# c_fan.net
KiCad netlist of a schematic drawn in Altium Designer
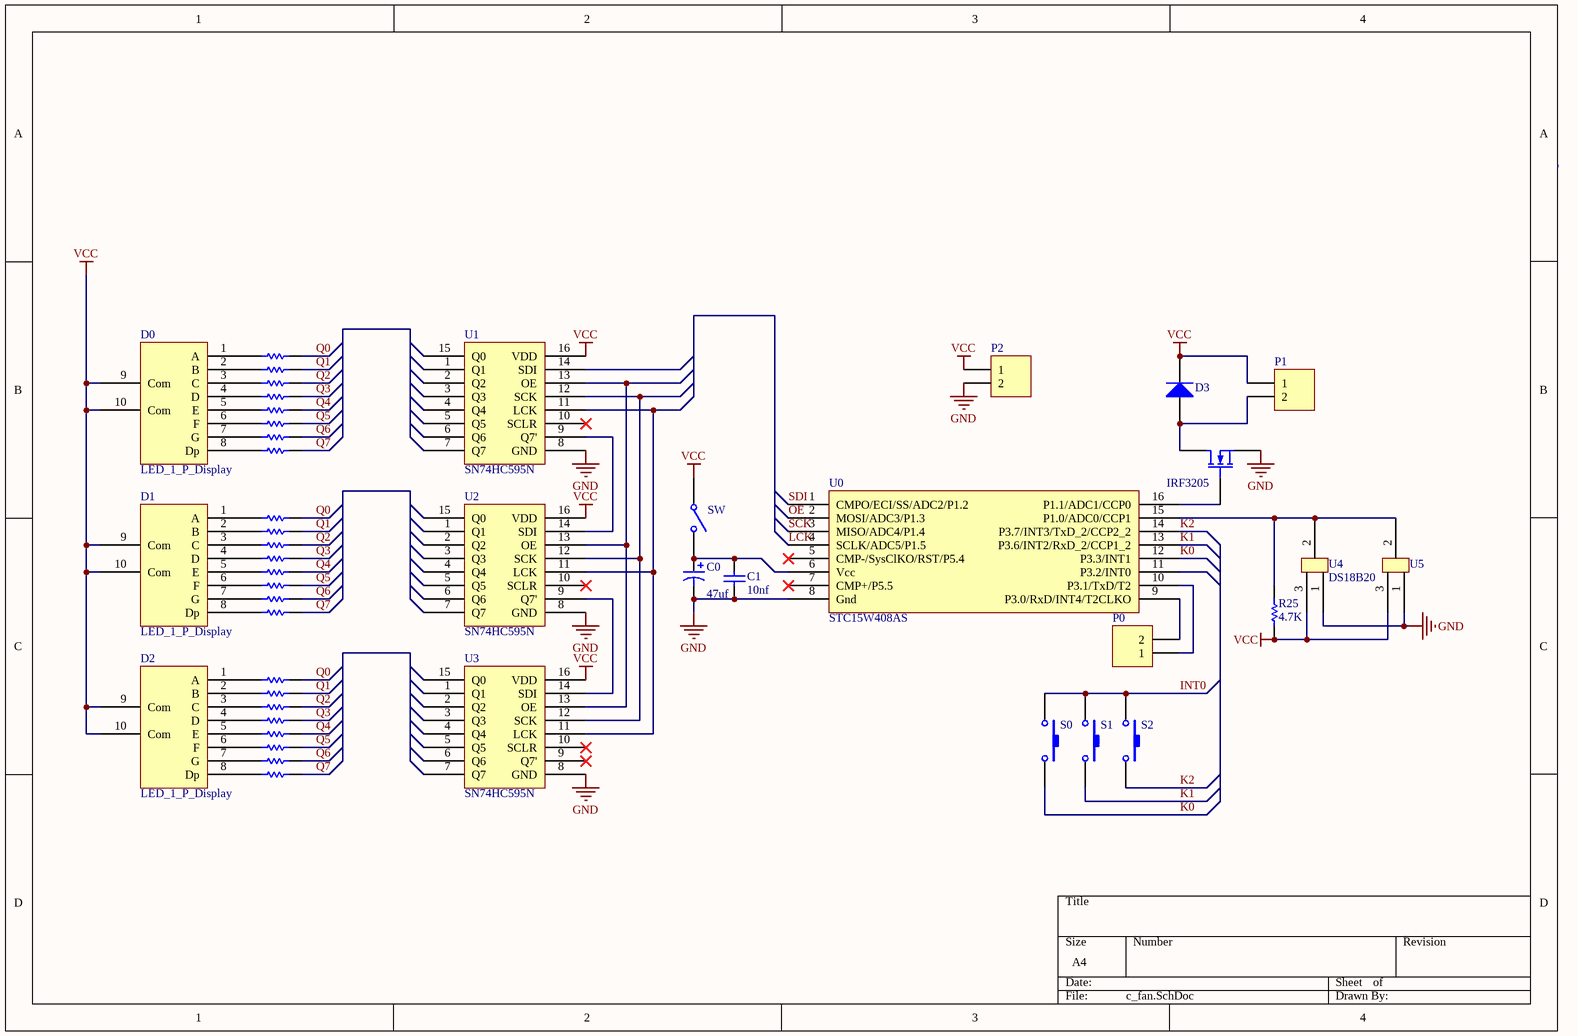
[diagram p0: c_fan.SchDoc]

(export (version "E")
  (design (tool "Eeschema 10.0.6"))
  (components
    (comp (ref "C0")
      (value "47uf")
      (footprint "C0805")
      (description "Polarized Capacitor (Surface Mount)")
      (fields (field (name "Comment") "Cap Pol3") (field (name "PUBLISHER") "Altium Limited"))
      (libsource (lib "Miscellaneous Devices") (part "Cap Pol3"))
    )
    (comp (ref "C1")
      (value "10nf")
      (footprint "C1206")
      (description "Capacitor (Semiconductor SIM Model)")
      (fields (field (name "Comment") "Cap Semi") (field (name "PUBLISHER") "Altium Limited"))
      (libsource (lib "Miscellaneous Devices") (part "Cap Semi"))
    )
    (comp (ref "D0")
      (value "LED_1_P_Display")
      (description "共阳一位")
      (libsource (lib "Self_establish") (part "LED_1_P_Display"))
    )
    (comp (ref "D1")
      (value "LED_1_P_Display")
      (description "共阳一位")
      (libsource (lib "Self_establish") (part "LED_1_P_Display"))
    )
    (comp (ref "D2")
      (value "LED_1_P_Display")
      (description "共阳一位")
      (libsource (lib "Self_establish") (part "LED_1_P_Display"))
    )
    (comp (ref "D3")
      (value "Diode")
      (footprint "SMC")
      (description "Default Diode")
      (fields (field (name "PUBLISHER") "Altium Limited"))
      (libsource (lib "Miscellaneous Devices") (part "Diode"))
    )
    (comp (ref "P0")
      (value "Header 2")
      (footprint "HDR1X2")
      (description "Header, 2-Pin")
      (fields (field (name "PUBLISHER") "Altium Limited"))
      (libsource (lib "Miscellaneous Connectors") (part "Header 2"))
    )
    (comp (ref "P1")
      (value "Header 2H")
      (footprint "HDR1X2H")
      (description "Header, 2-Pin, Right Angle")
      (fields (field (name "PUBLISHER") "Altium Limited"))
      (libsource (lib "Miscellaneous Connectors") (part "Header 2H"))
    )
    (comp (ref "P2")
      (value "Header 2H")
      (footprint "HDR1X2H")
      (description "Header, 2-Pin, Right Angle")
      (fields (field (name "PUBLISHER") "Altium Limited"))
      (libsource (lib "Miscellaneous Connectors") (part "Header 2H"))
    )
    (comp (ref "Q0")
      (value "IRF3205")
      (footprint "E3")
      (description "N-Channel MOSFET")
      (fields (field (name "PUBLISHER") "Altium Limited"))
      (libsource (lib "Miscellaneous Devices") (part "MOSFET-N"))
    )
    (comp (ref "R1")
      (value "Res1")
      (footprint "AXIAL-0.3")
      (description "Resistor")
      (fields (field (name "PUBLISHER") "Altium Limited"))
      (libsource (lib "Miscellaneous Devices") (part "Res1"))
    )
    (comp (ref "R2")
      (value "Res1")
      (footprint "AXIAL-0.3")
      (description "Resistor")
      (fields (field (name "PUBLISHER") "Altium Limited"))
      (libsource (lib "Miscellaneous Devices") (part "Res1"))
    )
    (comp (ref "R3")
      (value "Res1")
      (footprint "AXIAL-0.3")
      (description "Resistor")
      (fields (field (name "PUBLISHER") "Altium Limited"))
      (libsource (lib "Miscellaneous Devices") (part "Res1"))
    )
    (comp (ref "R4")
      (value "Res1")
      (footprint "AXIAL-0.3")
      (description "Resistor")
      (fields (field (name "PUBLISHER") "Altium Limited"))
      (libsource (lib "Miscellaneous Devices") (part "Res1"))
    )
    (comp (ref "R5")
      (value "Res1")
      (footprint "AXIAL-0.3")
      (description "Resistor")
      (fields (field (name "PUBLISHER") "Altium Limited"))
      (libsource (lib "Miscellaneous Devices") (part "Res1"))
    )
    (comp (ref "R6")
      (value "Res1")
      (footprint "AXIAL-0.3")
      (description "Resistor")
      (fields (field (name "PUBLISHER") "Altium Limited"))
      (libsource (lib "Miscellaneous Devices") (part "Res1"))
    )
    (comp (ref "R7")
      (value "Res1")
      (footprint "AXIAL-0.3")
      (description "Resistor")
      (fields (field (name "PUBLISHER") "Altium Limited"))
      (libsource (lib "Miscellaneous Devices") (part "Res1"))
    )
    (comp (ref "R8")
      (value "Res1")
      (footprint "AXIAL-0.3")
      (description "Resistor")
      (fields (field (name "PUBLISHER") "Altium Limited"))
      (libsource (lib "Miscellaneous Devices") (part "Res1"))
    )
    (comp (ref "R9")
      (value "Res1")
      (footprint "AXIAL-0.3")
      (description "Resistor")
      (fields (field (name "PUBLISHER") "Altium Limited"))
      (libsource (lib "Miscellaneous Devices") (part "Res1"))
    )
    (comp (ref "R10")
      (value "Res1")
      (footprint "AXIAL-0.3")
      (description "Resistor")
      (fields (field (name "PUBLISHER") "Altium Limited"))
      (libsource (lib "Miscellaneous Devices") (part "Res1"))
    )
    (comp (ref "R11")
      (value "Res1")
      (footprint "AXIAL-0.3")
      (description "Resistor")
      (fields (field (name "PUBLISHER") "Altium Limited"))
      (libsource (lib "Miscellaneous Devices") (part "Res1"))
    )
    (comp (ref "R12")
      (value "Res1")
      (footprint "AXIAL-0.3")
      (description "Resistor")
      (fields (field (name "PUBLISHER") "Altium Limited"))
      (libsource (lib "Miscellaneous Devices") (part "Res1"))
    )
    (comp (ref "R13")
      (value "Res1")
      (footprint "AXIAL-0.3")
      (description "Resistor")
      (fields (field (name "PUBLISHER") "Altium Limited"))
      (libsource (lib "Miscellaneous Devices") (part "Res1"))
    )
    (comp (ref "R14")
      (value "Res1")
      (footprint "AXIAL-0.3")
      (description "Resistor")
      (fields (field (name "PUBLISHER") "Altium Limited"))
      (libsource (lib "Miscellaneous Devices") (part "Res1"))
    )
    (comp (ref "R15")
      (value "Res1")
      (footprint "AXIAL-0.3")
      (description "Resistor")
      (fields (field (name "PUBLISHER") "Altium Limited"))
      (libsource (lib "Miscellaneous Devices") (part "Res1"))
    )
    (comp (ref "R16")
      (value "Res1")
      (footprint "AXIAL-0.3")
      (description "Resistor")
      (fields (field (name "PUBLISHER") "Altium Limited"))
      (libsource (lib "Miscellaneous Devices") (part "Res1"))
    )
    (comp (ref "R17")
      (value "Res1")
      (footprint "AXIAL-0.3")
      (description "Resistor")
      (fields (field (name "PUBLISHER") "Altium Limited"))
      (libsource (lib "Miscellaneous Devices") (part "Res1"))
    )
    (comp (ref "R18")
      (value "Res1")
      (footprint "AXIAL-0.3")
      (description "Resistor")
      (fields (field (name "PUBLISHER") "Altium Limited"))
      (libsource (lib "Miscellaneous Devices") (part "Res1"))
    )
    (comp (ref "R19")
      (value "Res1")
      (footprint "AXIAL-0.3")
      (description "Resistor")
      (fields (field (name "PUBLISHER") "Altium Limited"))
      (libsource (lib "Miscellaneous Devices") (part "Res1"))
    )
    (comp (ref "R20")
      (value "Res1")
      (footprint "AXIAL-0.3")
      (description "Resistor")
      (fields (field (name "PUBLISHER") "Altium Limited"))
      (libsource (lib "Miscellaneous Devices") (part "Res1"))
    )
    (comp (ref "R21")
      (value "Res1")
      (footprint "AXIAL-0.3")
      (description "Resistor")
      (fields (field (name "PUBLISHER") "Altium Limited"))
      (libsource (lib "Miscellaneous Devices") (part "Res1"))
    )
    (comp (ref "R22")
      (value "Res1")
      (footprint "AXIAL-0.3")
      (description "Resistor")
      (fields (field (name "PUBLISHER") "Altium Limited"))
      (libsource (lib "Miscellaneous Devices") (part "Res1"))
    )
    (comp (ref "R23")
      (value "Res1")
      (footprint "AXIAL-0.3")
      (description "Resistor")
      (fields (field (name "PUBLISHER") "Altium Limited"))
      (libsource (lib "Miscellaneous Devices") (part "Res1"))
    )
    (comp (ref "R24")
      (value "Res1")
      (footprint "AXIAL-0.3")
      (description "Resistor")
      (fields (field (name "PUBLISHER") "Altium Limited"))
      (libsource (lib "Miscellaneous Devices") (part "Res1"))
    )
    (comp (ref "R25")
      (value "4.7K")
      (footprint "AXIAL-0.3")
      (description "Resistor")
      (fields (field (name "Comment") "Res1") (field (name "PUBLISHER") "Altium Limited"))
      (libsource (lib "Miscellaneous Devices") (part "Res1"))
    )
    (comp (ref "S0")
      (value "SW-PB")
      (footprint "SPST-2")
      (description "Switch")
      (fields (field (name "PUBLISHER") "Altium Limited"))
      (libsource (lib "Miscellaneous Devices") (part "SW-PB"))
    )
    (comp (ref "S1")
      (value "SW-PB")
      (footprint "SPST-2")
      (description "Switch")
      (fields (field (name "PUBLISHER") "Altium Limited"))
      (libsource (lib "Miscellaneous Devices") (part "SW-PB"))
    )
    (comp (ref "S2")
      (value "SW-PB")
      (footprint "SPST-2")
      (description "Switch")
      (fields (field (name "PUBLISHER") "Altium Limited"))
      (libsource (lib "Miscellaneous Devices") (part "SW-PB"))
    )
    (comp (ref "SW")
      (value "SW-SPST")
      (footprint "SPST-2")
      (description "Single-Pole, Single-Throw Switch")
      (fields (field (name "PUBLISHER") "Altium Limited"))
      (libsource (lib "Miscellaneous Devices") (part "SW-SPST"))
    )
    (comp (ref "U0") (value "STC15W408AS") (libsource (lib "Self_establish") (part "STC15W408AS")))
    (comp (ref "U1") (value "SN74HC595N") (libsource (lib "Self_establish") (part "74HC595")))
    (comp (ref "U2") (value "SN74HC595N") (libsource (lib "Self_establish") (part "74HC595")))
    (comp (ref "U3") (value "SN74HC595N") (libsource (lib "Self_establish") (part "74HC595")))
    (comp (ref "U4") (value "DS18B20") (libsource (lib "Self_establish") (part "DS18B20")))
    (comp (ref "U5") (value "DS18B20") (libsource (lib "Self_establish") (part "DS18B20")))
  )
  (nets
    (net (code "1") (name "/INT0") (class "Default")
      (node (ref "S0") (pin "1") (pinfunction "1_1") (pintype "passive"))
      (node (ref "S1") (pin "1") (pinfunction "1_1") (pintype "passive"))
      (node (ref "S2") (pin "1") (pinfunction "1_1") (pintype "passive"))
    )
    (net (code "2") (name "/K0") (class "Default")
      (node (ref "S0") (pin "2") (pinfunction "2_2") (pintype "passive"))
      (node (ref "U0") (pin "12") (pinfunction "P3.3/INT1_12") (pintype "passive"))
    )
    (net (code "3") (name "/K1") (class "Default")
      (node (ref "S1") (pin "2") (pinfunction "2_2") (pintype "passive"))
      (node (ref "U0") (pin "13") (pinfunction "P3.6/INT2/RxD_2/CCP1_2_13") (pintype "passive"))
    )
    (net (code "4") (name "/K2") (class "Default")
      (node (ref "S2") (pin "2") (pinfunction "2_2") (pintype "passive"))
      (node (ref "U0") (pin "14") (pinfunction "P3.7/INT3/TxD_2/CCP2_2_14") (pintype "passive"))
    )
    (net (code "5") (name "/LCK") (class "Default")
      (node (ref "U0") (pin "4") (pinfunction "SCLK/ADC5/P1.5_4") (pintype "passive"))
    )
    (net (code "6") (name "/OE") (class "Default")
      (node (ref "U0") (pin "2") (pinfunction "MOSI/ADC3/P1.3_2") (pintype "passive"))
    )
    (net (code "7") (name "/Q0") (class "Default")
      (node (ref "R1") (pin "2") (pinfunction "2_2") (pintype "passive"))
      (node (ref "R17") (pin "2") (pinfunction "2_2") (pintype "passive"))
      (node (ref "R9") (pin "2") (pinfunction "2_2") (pintype "passive"))
    )
    (net (code "8") (name "/Q1") (class "Default")
      (node (ref "R10") (pin "2") (pinfunction "2_2") (pintype "passive"))
      (node (ref "R18") (pin "2") (pinfunction "2_2") (pintype "passive"))
      (node (ref "R2") (pin "2") (pinfunction "2_2") (pintype "passive"))
    )
    (net (code "9") (name "/Q2") (class "Default")
      (node (ref "R11") (pin "2") (pinfunction "2_2") (pintype "passive"))
      (node (ref "R19") (pin "2") (pinfunction "2_2") (pintype "passive"))
      (node (ref "R3") (pin "2") (pinfunction "2_2") (pintype "passive"))
    )
    (net (code "10") (name "/Q3") (class "Default")
      (node (ref "R12") (pin "2") (pinfunction "2_2") (pintype "passive"))
      (node (ref "R20") (pin "2") (pinfunction "2_2") (pintype "passive"))
      (node (ref "R4") (pin "2") (pinfunction "2_2") (pintype "passive"))
    )
    (net (code "11") (name "/Q4") (class "Default")
      (node (ref "R13") (pin "2") (pinfunction "2_2") (pintype "passive"))
      (node (ref "R21") (pin "2") (pinfunction "2_2") (pintype "passive"))
      (node (ref "R5") (pin "2") (pinfunction "2_2") (pintype "passive"))
    )
    (net (code "12") (name "/Q5") (class "Default")
      (node (ref "R14") (pin "2") (pinfunction "2_2") (pintype "passive"))
      (node (ref "R22") (pin "2") (pinfunction "2_2") (pintype "passive"))
      (node (ref "R6") (pin "2") (pinfunction "2_2") (pintype "passive"))
    )
    (net (code "13") (name "/Q6") (class "Default")
      (node (ref "R15") (pin "2") (pinfunction "2_2") (pintype "passive"))
      (node (ref "R23") (pin "2") (pinfunction "2_2") (pintype "passive"))
      (node (ref "R7") (pin "2") (pinfunction "2_2") (pintype "passive"))
    )
    (net (code "14") (name "/Q7") (class "Default")
      (node (ref "R16") (pin "2") (pinfunction "2_2") (pintype "passive"))
      (node (ref "R24") (pin "2") (pinfunction "2_2") (pintype "passive"))
      (node (ref "R8") (pin "2") (pinfunction "2_2") (pintype "passive"))
    )
    (net (code "15") (name "/SCK") (class "Default")
      (node (ref "U0") (pin "3") (pinfunction "MISO/ADC4/P1.4_3") (pintype "passive"))
    )
    (net (code "16") (name "/SDI") (class "Default")
      (node (ref "U0") (pin "1") (pinfunction "CMPO/ECI/SS/ADC2/P1.2_1") (pintype "passive"))
    )
    (net (code "17") (name "GND") (class "Default")
      (node (ref "C0") (pin "2") (pinfunction "2_2") (pintype "passive"))
      (node (ref "C1") (pin "1") (pinfunction "1_1") (pintype "passive"))
      (node (ref "P2") (pin "2") (pinfunction "2_2") (pintype "passive"))
      (node (ref "Q0") (pin "3") (pinfunction "S_3") (pintype "passive"))
      (node (ref "U0") (pin "8") (pinfunction "Gnd_8") (pintype "power_in"))
      (node (ref "U1") (pin "8") (pinfunction "GND_8") (pintype "passive"))
      (node (ref "U2") (pin "8") (pinfunction "GND_8") (pintype "passive"))
      (node (ref "U3") (pin "8") (pinfunction "GND_8") (pintype "passive"))
      (node (ref "U4") (pin "1") (pinfunction "GND_1") (pintype "passive"))
      (node (ref "U5") (pin "1") (pinfunction "GND_1") (pintype "passive"))
    )
    (net (code "18") (name "Net-(D0-A)") (class "Default")
      (node (ref "D0") (pin "1") (pinfunction "A_1") (pintype "passive"))
      (node (ref "R1") (pin "1") (pinfunction "1_1") (pintype "passive"))
    )
    (net (code "19") (name "Net-(D0-B)") (class "Default")
      (node (ref "D0") (pin "2") (pinfunction "B_2") (pintype "passive"))
      (node (ref "R2") (pin "1") (pinfunction "1_1") (pintype "passive"))
    )
    (net (code "20") (name "Net-(D0-C)") (class "Default")
      (node (ref "D0") (pin "3") (pinfunction "C_3") (pintype "passive"))
      (node (ref "R3") (pin "1") (pinfunction "1_1") (pintype "passive"))
    )
    (net (code "21") (name "Net-(D0-D)") (class "Default")
      (node (ref "D0") (pin "4") (pinfunction "D_4") (pintype "passive"))
      (node (ref "R4") (pin "1") (pinfunction "1_1") (pintype "passive"))
    )
    (net (code "22") (name "Net-(D0-Dp)") (class "Default")
      (node (ref "D0") (pin "8") (pinfunction "Dp_8") (pintype "passive"))
      (node (ref "R8") (pin "1") (pinfunction "1_1") (pintype "passive"))
    )
    (net (code "23") (name "Net-(D0-E)") (class "Default")
      (node (ref "D0") (pin "5") (pinfunction "E_5") (pintype "passive"))
      (node (ref "R5") (pin "1") (pinfunction "1_1") (pintype "passive"))
    )
    (net (code "24") (name "Net-(D0-F)") (class "Default")
      (node (ref "D0") (pin "6") (pinfunction "F_6") (pintype "passive"))
      (node (ref "R6") (pin "1") (pinfunction "1_1") (pintype "passive"))
    )
    (net (code "25") (name "Net-(D0-G)") (class "Default")
      (node (ref "D0") (pin "7") (pinfunction "G_7") (pintype "passive"))
      (node (ref "R7") (pin "1") (pinfunction "1_1") (pintype "passive"))
    )
    (net (code "26") (name "Net-(D1-A)") (class "Default")
      (node (ref "D1") (pin "1") (pinfunction "A_1") (pintype "passive"))
      (node (ref "R9") (pin "1") (pinfunction "1_1") (pintype "passive"))
    )
    (net (code "27") (name "Net-(D1-B)") (class "Default")
      (node (ref "D1") (pin "2") (pinfunction "B_2") (pintype "passive"))
      (node (ref "R10") (pin "1") (pinfunction "1_1") (pintype "passive"))
    )
    (net (code "28") (name "Net-(D1-C)") (class "Default")
      (node (ref "D1") (pin "3") (pinfunction "C_3") (pintype "passive"))
      (node (ref "R11") (pin "1") (pinfunction "1_1") (pintype "passive"))
    )
    (net (code "29") (name "Net-(D1-D)") (class "Default")
      (node (ref "D1") (pin "4") (pinfunction "D_4") (pintype "passive"))
      (node (ref "R12") (pin "1") (pinfunction "1_1") (pintype "passive"))
    )
    (net (code "30") (name "Net-(D1-Dp)") (class "Default")
      (node (ref "D1") (pin "8") (pinfunction "Dp_8") (pintype "passive"))
      (node (ref "R16") (pin "1") (pinfunction "1_1") (pintype "passive"))
    )
    (net (code "31") (name "Net-(D1-E)") (class "Default")
      (node (ref "D1") (pin "5") (pinfunction "E_5") (pintype "passive"))
      (node (ref "R13") (pin "1") (pinfunction "1_1") (pintype "passive"))
    )
    (net (code "32") (name "Net-(D1-F)") (class "Default")
      (node (ref "D1") (pin "6") (pinfunction "F_6") (pintype "passive"))
      (node (ref "R14") (pin "1") (pinfunction "1_1") (pintype "passive"))
    )
    (net (code "33") (name "Net-(D1-G)") (class "Default")
      (node (ref "D1") (pin "7") (pinfunction "G_7") (pintype "passive"))
      (node (ref "R15") (pin "1") (pinfunction "1_1") (pintype "passive"))
    )
    (net (code "34") (name "Net-(D2-A)") (class "Default")
      (node (ref "D2") (pin "1") (pinfunction "A_1") (pintype "passive"))
      (node (ref "R17") (pin "1") (pinfunction "1_1") (pintype "passive"))
    )
    (net (code "35") (name "Net-(D2-B)") (class "Default")
      (node (ref "D2") (pin "2") (pinfunction "B_2") (pintype "passive"))
      (node (ref "R18") (pin "1") (pinfunction "1_1") (pintype "passive"))
    )
    (net (code "36") (name "Net-(D2-C)") (class "Default")
      (node (ref "D2") (pin "3") (pinfunction "C_3") (pintype "passive"))
      (node (ref "R19") (pin "1") (pinfunction "1_1") (pintype "passive"))
    )
    (net (code "37") (name "Net-(D2-D)") (class "Default")
      (node (ref "D2") (pin "4") (pinfunction "D_4") (pintype "passive"))
      (node (ref "R20") (pin "1") (pinfunction "1_1") (pintype "passive"))
    )
    (net (code "38") (name "Net-(D2-Dp)") (class "Default")
      (node (ref "D2") (pin "8") (pinfunction "Dp_8") (pintype "passive"))
      (node (ref "R24") (pin "1") (pinfunction "1_1") (pintype "passive"))
    )
    (net (code "39") (name "Net-(D2-E)") (class "Default")
      (node (ref "D2") (pin "5") (pinfunction "E_5") (pintype "passive"))
      (node (ref "R21") (pin "1") (pinfunction "1_1") (pintype "passive"))
    )
    (net (code "40") (name "Net-(D2-F)") (class "Default")
      (node (ref "D2") (pin "6") (pinfunction "F_6") (pintype "passive"))
      (node (ref "R22") (pin "1") (pinfunction "1_1") (pintype "passive"))
    )
    (net (code "41") (name "Net-(D2-G)") (class "Default")
      (node (ref "D2") (pin "7") (pinfunction "G_7") (pintype "passive"))
      (node (ref "R23") (pin "1") (pinfunction "1_1") (pintype "passive"))
    )
    (net (code "42") (name "Net-(D3-A)") (class "Default")
      (node (ref "D3") (pin "1") (pinfunction "A_1") (pintype "passive"))
      (node (ref "P1") (pin "2") (pinfunction "2_2") (pintype "passive"))
      (node (ref "Q0") (pin "1") (pinfunction "D_1") (pintype "passive"))
    )
    (net (code "43") (name "Net-(Q0-G)") (class "Default")
      (node (ref "Q0") (pin "2") (pinfunction "G_2") (pintype "passive"))
      (node (ref "U0") (pin "16") (pinfunction "P1.1/ADC1/CCP0_16") (pintype "passive"))
    )
    (net (code "44") (name "Net-(SW-NO)") (class "Default")
      (node (ref "C0") (pin "1") (pinfunction "1_1") (pintype "passive"))
      (node (ref "C1") (pin "2") (pinfunction "2_2") (pintype "passive"))
      (node (ref "SW") (pin "2") (pinfunction "NO_2") (pintype "passive"))
      (node (ref "U0") (pin "6") (pinfunction "Vcc_6") (pintype "power_in"))
    )
    (net (code "45") (name "Net-(U0-P1.0{slash}ADC0{slash}CCP1)") (class "Default")
      (node (ref "R25") (pin "1") (pinfunction "1_1") (pintype "passive"))
      (node (ref "U0") (pin "15") (pinfunction "P1.0/ADC0/CCP1_15") (pintype "passive"))
      (node (ref "U4") (pin "2") (pinfunction "DQ_2") (pintype "passive"))
      (node (ref "U5") (pin "2") (pinfunction "DQ_2") (pintype "passive"))
    )
    (net (code "46") (name "Net-(U0-P3.0{slash}RxD{slash}INT4{slash}T2CLKO)") (class "Default")
      (node (ref "P0") (pin "2") (pinfunction "2_2") (pintype "passive"))
      (node (ref "U0") (pin "9") (pinfunction "P3.0/RxD/INT4/T2CLKO_9") (pintype "passive"))
    )
    (net (code "47") (name "Net-(U0-P3.1{slash}TxD{slash}T2)") (class "Default")
      (node (ref "P0") (pin "1") (pinfunction "1_1") (pintype "passive"))
      (node (ref "U0") (pin "10") (pinfunction "P3.1/TxD/T2_10") (pintype "passive"))
    )
    (net (code "48") (name "Net-(U1-LCK)") (class "Default")
      (node (ref "U1") (pin "11") (pinfunction "LCK_11") (pintype "passive"))
      (node (ref "U2") (pin "11") (pinfunction "LCK_11") (pintype "passive"))
      (node (ref "U3") (pin "11") (pinfunction "LCK_11") (pintype "passive"))
    )
    (net (code "49") (name "Net-(U1-OE)") (class "Default")
      (node (ref "U1") (pin "13") (pinfunction "OE_13") (pintype "passive"))
      (node (ref "U2") (pin "13") (pinfunction "OE_13") (pintype "passive"))
      (node (ref "U3") (pin "13") (pinfunction "OE_13") (pintype "passive"))
    )
    (net (code "50") (name "Net-(U1-Q7')") (class "Default")
      (node (ref "U1") (pin "9") (pinfunction "Q7'_9") (pintype "passive"))
      (node (ref "U2") (pin "14") (pinfunction "SDI_14") (pintype "passive"))
    )
    (net (code "51") (name "Net-(U1-SCK)") (class "Default")
      (node (ref "U1") (pin "12") (pinfunction "SCK_12") (pintype "passive"))
      (node (ref "U2") (pin "12") (pinfunction "SCK_12") (pintype "passive"))
      (node (ref "U3") (pin "12") (pinfunction "SCK_12") (pintype "passive"))
    )
    (net (code "52") (name "Net-(U2-Q7')") (class "Default")
      (node (ref "U2") (pin "9") (pinfunction "Q7'_9") (pintype "passive"))
      (node (ref "U3") (pin "14") (pinfunction "SDI_14") (pintype "passive"))
    )
    (net (code "53") (name "VCC") (class "Default")
      (node (ref "D0") (pin "10") (pinfunction "Com_10") (pintype "passive"))
      (node (ref "D0") (pin "9") (pinfunction "Com_9") (pintype "passive"))
      (node (ref "D1") (pin "10") (pinfunction "Com_10") (pintype "passive"))
      (node (ref "D1") (pin "9") (pinfunction "Com_9") (pintype "passive"))
      (node (ref "D2") (pin "10") (pinfunction "Com_10") (pintype "passive"))
      (node (ref "D2") (pin "9") (pinfunction "Com_9") (pintype "passive"))
      (node (ref "D3") (pin "2") (pinfunction "K_2") (pintype "passive"))
      (node (ref "P1") (pin "1") (pinfunction "1_1") (pintype "passive"))
      (node (ref "P2") (pin "1") (pinfunction "1_1") (pintype "passive"))
      (node (ref "R25") (pin "2") (pinfunction "2_2") (pintype "passive"))
      (node (ref "SW") (pin "1") (pinfunction "COMMON_1") (pintype "passive"))
      (node (ref "U1") (pin "16") (pinfunction "VDD_16") (pintype "passive"))
      (node (ref "U2") (pin "16") (pinfunction "VDD_16") (pintype "passive"))
      (node (ref "U3") (pin "16") (pinfunction "VDD_16") (pintype "passive"))
      (node (ref "U4") (pin "3") (pinfunction "VDD_3") (pintype "passive"))
      (node (ref "U5") (pin "3") (pinfunction "VDD_3") (pintype "passive"))
    )
    (net (code "54") (name "unconnected-(U0-CMP+{slash}P5.5-Pad7)") (class "Default")
      (node (ref "U0") (pin "7") (pinfunction "CMP+/P5.5_7") (pintype "passive+no_connect"))
    )
    (net (code "55") (name "unconnected-(U0-CMP-{slash}SysClKO{slash}RST{slash}P5.4-Pad5)") (class "Default")
      (node (ref "U0") (pin "5") (pinfunction "CMP-/SysClKO/RST/P5.4_5") (pintype "passive+no_connect"))
    )
    (net (code "56") (name "unconnected-(U0-P3.2{slash}INT0-Pad11)") (class "Default")
      (node (ref "U0") (pin "11") (pinfunction "P3.2/INT0_11") (pintype "passive"))
    )
    (net (code "57") (name "unconnected-(U1-Q0-Pad15)") (class "Default")
      (node (ref "U1") (pin "15") (pinfunction "Q0_15") (pintype "passive"))
    )
    (net (code "58") (name "unconnected-(U1-Q1-Pad1)") (class "Default")
      (node (ref "U1") (pin "1") (pinfunction "Q1_1") (pintype "passive"))
    )
    (net (code "59") (name "unconnected-(U1-Q2-Pad2)") (class "Default")
      (node (ref "U1") (pin "2") (pinfunction "Q2_2") (pintype "passive"))
    )
    (net (code "60") (name "unconnected-(U1-Q3-Pad3)") (class "Default")
      (node (ref "U1") (pin "3") (pinfunction "Q3_3") (pintype "passive"))
    )
    (net (code "61") (name "unconnected-(U1-Q4-Pad4)") (class "Default")
      (node (ref "U1") (pin "4") (pinfunction "Q4_4") (pintype "passive"))
    )
    (net (code "62") (name "unconnected-(U1-Q5-Pad5)") (class "Default")
      (node (ref "U1") (pin "5") (pinfunction "Q5_5") (pintype "passive"))
    )
    (net (code "63") (name "unconnected-(U1-Q6-Pad6)") (class "Default")
      (node (ref "U1") (pin "6") (pinfunction "Q6_6") (pintype "passive"))
    )
    (net (code "64") (name "unconnected-(U1-Q7-Pad7)") (class "Default")
      (node (ref "U1") (pin "7") (pinfunction "Q7_7") (pintype "passive"))
    )
    (net (code "65") (name "unconnected-(U1-SCLR-Pad10)") (class "Default")
      (node (ref "U1") (pin "10") (pinfunction "SCLR_10") (pintype "passive+no_connect"))
    )
    (net (code "66") (name "unconnected-(U1-SDI-Pad14)") (class "Default")
      (node (ref "U1") (pin "14") (pinfunction "SDI_14") (pintype "passive"))
    )
    (net (code "67") (name "unconnected-(U2-Q0-Pad15)") (class "Default")
      (node (ref "U2") (pin "15") (pinfunction "Q0_15") (pintype "passive"))
    )
    (net (code "68") (name "unconnected-(U2-Q1-Pad1)") (class "Default")
      (node (ref "U2") (pin "1") (pinfunction "Q1_1") (pintype "passive"))
    )
    (net (code "69") (name "unconnected-(U2-Q2-Pad2)") (class "Default")
      (node (ref "U2") (pin "2") (pinfunction "Q2_2") (pintype "passive"))
    )
    (net (code "70") (name "unconnected-(U2-Q3-Pad3)") (class "Default")
      (node (ref "U2") (pin "3") (pinfunction "Q3_3") (pintype "passive"))
    )
    (net (code "71") (name "unconnected-(U2-Q4-Pad4)") (class "Default")
      (node (ref "U2") (pin "4") (pinfunction "Q4_4") (pintype "passive"))
    )
    (net (code "72") (name "unconnected-(U2-Q5-Pad5)") (class "Default")
      (node (ref "U2") (pin "5") (pinfunction "Q5_5") (pintype "passive"))
    )
    (net (code "73") (name "unconnected-(U2-Q6-Pad6)") (class "Default")
      (node (ref "U2") (pin "6") (pinfunction "Q6_6") (pintype "passive"))
    )
    (net (code "74") (name "unconnected-(U2-Q7-Pad7)") (class "Default")
      (node (ref "U2") (pin "7") (pinfunction "Q7_7") (pintype "passive"))
    )
    (net (code "75") (name "unconnected-(U2-SCLR-Pad10)") (class "Default")
      (node (ref "U2") (pin "10") (pinfunction "SCLR_10") (pintype "passive+no_connect"))
    )
    (net (code "76") (name "unconnected-(U3-Q0-Pad15)") (class "Default")
      (node (ref "U3") (pin "15") (pinfunction "Q0_15") (pintype "passive"))
    )
    (net (code "77") (name "unconnected-(U3-Q1-Pad1)") (class "Default")
      (node (ref "U3") (pin "1") (pinfunction "Q1_1") (pintype "passive"))
    )
    (net (code "78") (name "unconnected-(U3-Q2-Pad2)") (class "Default")
      (node (ref "U3") (pin "2") (pinfunction "Q2_2") (pintype "passive"))
    )
    (net (code "79") (name "unconnected-(U3-Q3-Pad3)") (class "Default")
      (node (ref "U3") (pin "3") (pinfunction "Q3_3") (pintype "passive"))
    )
    (net (code "80") (name "unconnected-(U3-Q4-Pad4)") (class "Default")
      (node (ref "U3") (pin "4") (pinfunction "Q4_4") (pintype "passive"))
    )
    (net (code "81") (name "unconnected-(U3-Q5-Pad5)") (class "Default")
      (node (ref "U3") (pin "5") (pinfunction "Q5_5") (pintype "passive"))
    )
    (net (code "82") (name "unconnected-(U3-Q6-Pad6)") (class "Default")
      (node (ref "U3") (pin "6") (pinfunction "Q6_6") (pintype "passive"))
    )
    (net (code "83") (name "unconnected-(U3-Q7'-Pad9)") (class "Default")
      (node (ref "U3") (pin "9") (pinfunction "Q7'_9") (pintype "passive+no_connect"))
    )
    (net (code "84") (name "unconnected-(U3-Q7-Pad7)") (class "Default")
      (node (ref "U3") (pin "7") (pinfunction "Q7_7") (pintype "passive"))
    )
    (net (code "85") (name "unconnected-(U3-SCLR-Pad10)") (class "Default")
      (node (ref "U3") (pin "10") (pinfunction "SCLR_10") (pintype "passive+no_connect"))
    )
  )
)
